# driver_ckt_component.net
KiCad netlist of a schematic drawn in EAGLE
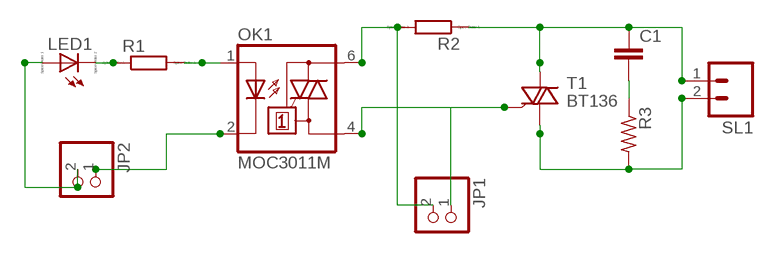
[diagram p0: schematic, sheet 1]

(export (version "E")
  (design (tool "Eeschema 10.0.6"))
  (components
    (comp (ref "C1")
      (value "C5/2.5")
      (footprint "eagle-import:C5B2.5")
      (libsource (lib "eagle-import") (part "C5/2.5"))
    )
    (comp (ref "JP1")
      (value "PINHD-1X2")
      (footprint "eagle-import:1X02")
      (libsource (lib "eagle-import") (part "PINHD-1X2"))
    )
    (comp (ref "JP2")
      (value "PINHD-1X2")
      (footprint "eagle-import:1X02")
      (libsource (lib "eagle-import") (part "PINHD-1X2"))
    )
    (comp (ref "LED1")
      (value "LED_E")
      (footprint "eagle-import:LED_1206")
      (libsource (lib "eagle-import") (part "LED_E"))
    )
    (comp (ref "OK1")
      (value "MOC3011M")
      (footprint "eagle-import:DIL06")
      (fields (field (name "MF") "FAIRCHILD SEMICONDUCTOR") (field (name "MPN") "MOC3011-M"))
      (libsource (lib "eagle-import") (part "MOC30M11"))
    )
    (comp (ref "R1")
      (value "R0204/7")
      (footprint "eagle-import:0204_7")
      (libsource (lib "eagle-import") (part "R0204/7"))
    )
    (comp (ref "R2")
      (value "R0204/7")
      (footprint "eagle-import:0204_7")
      (libsource (lib "eagle-import") (part "R0204/7"))
    )
    (comp (ref "R3")
      (value "R-US_0411/15")
      (footprint "eagle-import:0411_15")
      (libsource (lib "eagle-import") (part "R-US_0411/15"))
    )
    (comp (ref "SL1")
      (value "M02")
      (footprint "eagle-import:02P")
      (libsource (lib "eagle-import") (part "M02"))
    )
    (comp (ref "T1")
      (value "BT136")
      (footprint "eagle-import:TO220AB")
      (libsource (lib "eagle-import") (part "BT136"))
    )
  )
  (nets
    (net (code "1") (name "Net-(C1-Pad2)") (class "Default")
      (node (ref "C1") (pin "2") (pinfunction "2_2") (pintype "passive"))
      (node (ref "R3") (pin "1") (pinfunction "1_1") (pintype "passive"))
    )
    (net (code "2") (name "Net-(JP2-Pad2)") (class "Default")
      (node (ref "JP2") (pin "2") (pinfunction "2_2") (pintype "passive"))
      (node (ref "LED1") (pin "A") (pinfunction "A_A") (pintype "passive"))
    )
    (net (code "3") (name "Net-(LED1-PadC)") (class "Default")
      (node (ref "LED1") (pin "C") (pinfunction "C_C") (pintype "passive"))
      (node (ref "R1") (pin "1") (pinfunction "1_1") (pintype "passive"))
    )
    (net (code "4") (name "Net-(OK1-A)") (class "Default")
      (node (ref "OK1") (pin "1") (pinfunction "A_1") (pintype "passive"))
      (node (ref "R1") (pin "2") (pinfunction "2_2") (pintype "passive"))
    )
    (net (code "5") (name "Net-(OK1-A1)") (class "Default")
      (node (ref "JP1") (pin "1") (pinfunction "1_1") (pintype "passive"))
      (node (ref "OK1") (pin "4") (pinfunction "A1_4") (pintype "passive"))
      (node (ref "T1") (pin "3") (pinfunction "G_3") (pintype "passive"))
    )
    (net (code "6") (name "Net-(OK1-A2)") (class "Default")
      (node (ref "JP1") (pin "2") (pinfunction "2_2") (pintype "passive"))
      (node (ref "OK1") (pin "6") (pinfunction "A2_6") (pintype "passive"))
      (node (ref "R2") (pin "2") (pinfunction "2_2") (pintype "passive"))
    )
    (net (code "7") (name "Net-(OK1-C)") (class "Default")
      (node (ref "JP2") (pin "1") (pinfunction "1_1") (pintype "passive"))
      (node (ref "OK1") (pin "2") (pinfunction "C_2") (pintype "passive"))
    )
    (net (code "8") (name "Net-(T1-A1)") (class "Default")
      (node (ref "R3") (pin "2") (pinfunction "2_2") (pintype "passive"))
      (node (ref "SL1") (pin "2") (pinfunction "2_2") (pintype "passive"))
      (node (ref "T1") (pin "1") (pinfunction "A1_1") (pintype "passive"))
    )
    (net (code "9") (name "Net-(T1-A2)") (class "Default")
      (node (ref "C1") (pin "1") (pinfunction "1_1") (pintype "passive"))
      (node (ref "R2") (pin "1") (pinfunction "1_1") (pintype "passive"))
      (node (ref "SL1") (pin "1") (pinfunction "1_1") (pintype "passive"))
      (node (ref "T1") (pin "2") (pinfunction "A2_2") (pintype "passive"))
    )
  )
)
